# Sheet1.net
KiCad netlist of a schematic drawn in Altium Designer
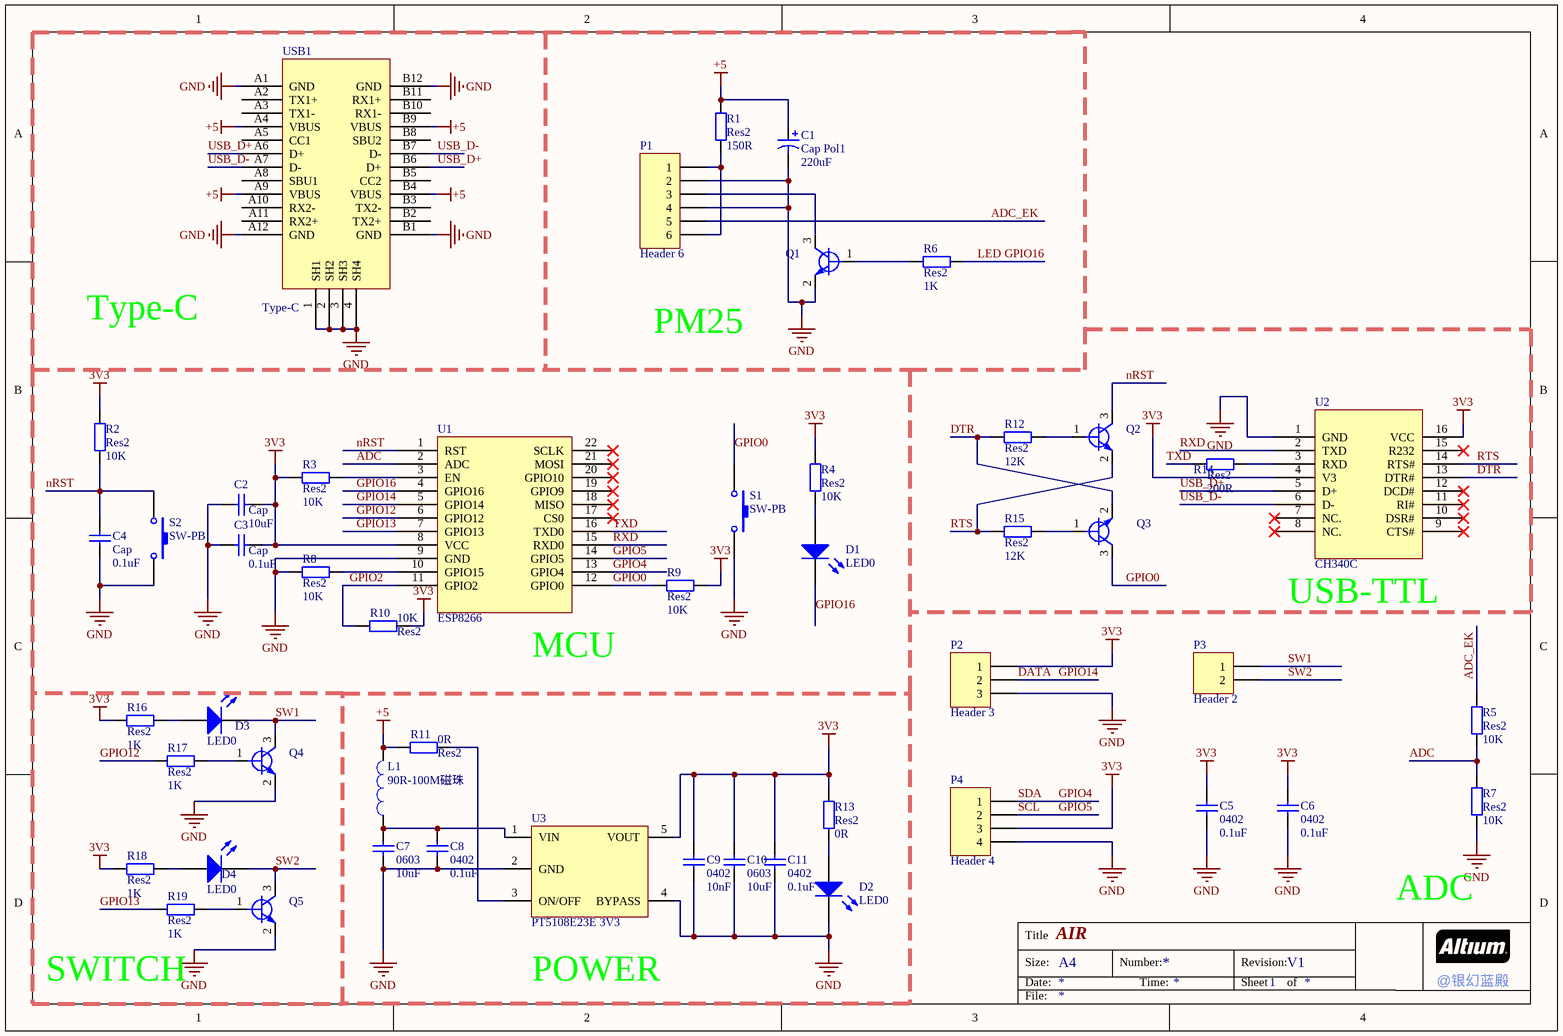
[diagram p0: Sheet1.SchDoc]

(export (version "E")
  (design (tool "Eeschema 10.0.6"))
  (components
    (comp (ref "C1")
      (value "Cap Pol1")
      (footprint "CAP 2.5*6.3*11.2")
      (description "Polarized Capacitor (Radial)")
      (fields (field (name "ALTIUM_VALUE") "220uF") (field (name "PUBLISHER") "Altium Limited"))
      (libsource (lib "Miscellaneous Devices") (part "Cap Pol1"))
    )
    (comp (ref "C2")
      (value "Cap")
      (footprint "C 0402_M")
      (description "Capacitor")
      (fields (field (name "ALTIUM_VALUE") "10uF") (field (name "PUBLISHER") "Altium Limited"))
      (libsource (lib "Miscellaneous Devices") (part "Cap"))
    )
    (comp (ref "C3")
      (value "Cap")
      (footprint "C 0402_M")
      (description "Capacitor")
      (fields (field (name "ALTIUM_VALUE") "0.1uF") (field (name "PUBLISHER") "Altium Limited"))
      (libsource (lib "Miscellaneous Devices") (part "Cap"))
    )
    (comp (ref "C4")
      (value "Cap")
      (footprint "C 0402_M")
      (description "Capacitor")
      (fields (field (name "ALTIUM_VALUE") "0.1uF") (field (name "PUBLISHER") "Altium Limited"))
      (libsource (lib "Miscellaneous Devices") (part "Cap"))
    )
    (comp (ref "C5")
      (value "0402")
      (footprint "C 0402_M")
      (description "Capacitor (Semiconductor SIM Model)")
      (fields (field (name "ALTIUM_VALUE") "0.1uF") (field (name "PUBLISHER") "Altium Limited"))
      (libsource (lib "Miscellaneous Devices") (part "Cap Semi"))
    )
    (comp (ref "C6")
      (value "0402")
      (footprint "C 0402_M")
      (description "Capacitor (Semiconductor SIM Model)")
      (fields (field (name "ALTIUM_VALUE") "0.1uF") (field (name "PUBLISHER") "Altium Limited"))
      (libsource (lib "Miscellaneous Devices") (part "Cap Semi"))
    )
    (comp (ref "C7")
      (value "0603")
      (footprint "C 0603_M")
      (description "Capacitor (Semiconductor SIM Model)")
      (fields (field (name "ALTIUM_VALUE") "10uF") (field (name "PUBLISHER") "Altium Limited"))
      (libsource (lib "Miscellaneous Devices") (part "Cap Semi"))
    )
    (comp (ref "C8")
      (value "0402")
      (footprint "C 0402_M")
      (description "Capacitor (Semiconductor SIM Model)")
      (fields (field (name "ALTIUM_VALUE") "0.1uF") (field (name "PUBLISHER") "Altium Limited"))
      (libsource (lib "Miscellaneous Devices") (part "Cap Semi"))
    )
    (comp (ref "C9")
      (value "0402")
      (footprint "C 0402_M")
      (description "Capacitor (Semiconductor SIM Model)")
      (fields (field (name "ALTIUM_VALUE") "10nF") (field (name "PUBLISHER") "Altium Limited"))
      (libsource (lib "Miscellaneous Devices") (part "Cap Semi"))
    )
    (comp (ref "C10")
      (value "0603")
      (footprint "C 0603_M")
      (description "Capacitor (Semiconductor SIM Model)")
      (fields (field (name "ALTIUM_VALUE") "10uF") (field (name "PUBLISHER") "Altium Limited"))
      (libsource (lib "Miscellaneous Devices") (part "Cap Semi"))
    )
    (comp (ref "C11")
      (value "0402")
      (footprint "C 0402_M")
      (description "Capacitor (Semiconductor SIM Model)")
      (fields (field (name "ALTIUM_VALUE") "0.1uF") (field (name "PUBLISHER") "Altium Limited"))
      (libsource (lib "Miscellaneous Devices") (part "Cap Semi"))
    )
    (comp (ref "D1")
      (value "LED0")
      (footprint "LED 0603R")
      (description "Typical INFRARED GaAs LED")
      (fields (field (name "PUBLISHER") "Altium Limited"))
      (libsource (lib "Miscellaneous Devices") (part "LED0"))
    )
    (comp (ref "D2")
      (value "LED0")
      (footprint "LED 0603R")
      (description "Typical INFRARED GaAs LED")
      (fields (field (name "PUBLISHER") "Altium Limited"))
      (libsource (lib "Miscellaneous Devices") (part "LED0"))
    )
    (comp (ref "D3")
      (value "LED0")
      (footprint "LED 0603R")
      (description "Typical INFRARED GaAs LED")
      (fields (field (name "PUBLISHER") "Altium Limited"))
      (libsource (lib "Miscellaneous Devices") (part "LED0"))
    )
    (comp (ref "D4")
      (value "LED0")
      (footprint "LED 0603R")
      (description "Typical INFRARED GaAs LED")
      (fields (field (name "PUBLISHER") "Altium Limited"))
      (libsource (lib "Miscellaneous Devices") (part "LED0"))
    )
    (comp (ref "L1")
      (value "90R-100M磁珠")
      (footprint "R 0603_M")
      (libsource (lib "手枪") (part "L,10UH,1.7A,S5*5*4.7,0.093Ω_1"))
    )
    (comp (ref "P1")
      (value "Header 6")
      (footprint "HDR1X6")
      (description "Header, 6-Pin")
      (fields (field (name "PUBLISHER") "Altium Limited"))
      (libsource (lib "Miscellaneous Connectors") (part "Header 6"))
    )
    (comp (ref "P2")
      (value "Header 3")
      (footprint "HDR1X3")
      (description "Header, 3-Pin")
      (fields (field (name "PUBLISHER") "Altium Limited"))
      (libsource (lib "Miscellaneous Connectors") (part "Header 3"))
    )
    (comp (ref "P3")
      (value "Header 2")
      (footprint "HDR1X2")
      (description "Header, 2-Pin")
      (fields (field (name "PUBLISHER") "Altium Limited"))
      (libsource (lib "Miscellaneous Connectors") (part "Header 2"))
    )
    (comp (ref "P4")
      (value "Header 4")
      (footprint "HDR1X4")
      (description "Header, 4-Pin")
      (fields (field (name "PUBLISHER") "Altium Limited"))
      (libsource (lib "Miscellaneous Connectors") (part "Header 4"))
    )
    (comp (ref "Q1")
      (value "Y1 NPN SOT23-3")
      (footprint "SMT_TRIODE_NPN")
      (libsource (lib "DDJ_20180904_Library") (part "S8050"))
    )
    (comp (ref "Q2")
      (value "Y1 NPN SOT23-3")
      (footprint "SMT_TRIODE_NPN")
      (libsource (lib "DDJ_20180904_Library") (part "S8050"))
    )
    (comp (ref "Q3")
      (value "Y1 NPN SOT23-3")
      (footprint "SMT_TRIODE_NPN")
      (libsource (lib "DDJ_20180904_Library") (part "S8050"))
    )
    (comp (ref "Q4")
      (value "Y1 NPN SOT23-3")
      (footprint "SMT_TRIODE_NPN")
      (libsource (lib "DDJ_20180904_Library") (part "S8050"))
    )
    (comp (ref "Q5")
      (value "Y1 NPN SOT23-3")
      (footprint "SMT_TRIODE_NPN")
      (libsource (lib "DDJ_20180904_Library") (part "S8050"))
    )
    (comp (ref "R1")
      (value "Res2")
      (footprint "R 0402_M")
      (description "Resistor")
      (fields (field (name "ALTIUM_VALUE") "150R") (field (name "PUBLISHER") "Altium Limited"))
      (libsource (lib "") (part "Res2_3"))
    )
    (comp (ref "R2")
      (value "Res2")
      (footprint "R 0402_M")
      (description "Resistor")
      (fields (field (name "ALTIUM_VALUE") "10K") (field (name "PUBLISHER") "Altium Limited"))
      (libsource (lib "") (part "Res2_2"))
    )
    (comp (ref "R3")
      (value "Res2")
      (footprint "R 0402_M")
      (description "Resistor")
      (fields (field (name "ALTIUM_VALUE") "10K") (field (name "PUBLISHER") "Altium Limited"))
      (libsource (lib "Miscellaneous Devices") (part "Res2"))
    )
    (comp (ref "R4")
      (value "Res2")
      (footprint "R 0402_M")
      (description "Resistor")
      (fields (field (name "ALTIUM_VALUE") "10K") (field (name "PUBLISHER") "Altium Limited"))
      (libsource (lib "") (part "Res2_2"))
    )
    (comp (ref "R5")
      (value "Res2")
      (footprint "R 0402_M")
      (description "Resistor")
      (fields (field (name "ALTIUM_VALUE") "10K") (field (name "PUBLISHER") "Altium Limited"))
      (libsource (lib "") (part "Res2_2"))
    )
    (comp (ref "R6")
      (value "Res2")
      (footprint "R 0402_M")
      (description "Resistor")
      (fields (field (name "ALTIUM_VALUE") "1K") (field (name "PUBLISHER") "Altium Limited"))
      (libsource (lib "") (part "Res2_1"))
    )
    (comp (ref "R7")
      (value "Res2")
      (footprint "R 0402_M")
      (description "Resistor")
      (fields (field (name "ALTIUM_VALUE") "10K") (field (name "PUBLISHER") "Altium Limited"))
      (libsource (lib "") (part "Res2_2"))
    )
    (comp (ref "R8")
      (value "Res2")
      (footprint "R 0402_M")
      (description "Resistor")
      (fields (field (name "ALTIUM_VALUE") "10K") (field (name "PUBLISHER") "Altium Limited"))
      (libsource (lib "Miscellaneous Devices") (part "Res2"))
    )
    (comp (ref "R9")
      (value "Res2")
      (footprint "R 0402_M")
      (description "Resistor")
      (fields (field (name "ALTIUM_VALUE") "10K") (field (name "PUBLISHER") "Altium Limited"))
      (libsource (lib "Miscellaneous Devices") (part "Res2"))
    )
    (comp (ref "R10")
      (value "Res2")
      (footprint "R 0402_M")
      (description "Resistor")
      (fields (field (name "ALTIUM_VALUE") "10K") (field (name "PUBLISHER") "Altium Limited"))
      (libsource (lib "Miscellaneous Devices") (part "Res2"))
    )
    (comp (ref "R11")
      (value "Res2")
      (footprint "R 0402_M")
      (description "Resistor")
      (fields (field (name "ALTIUM_VALUE") "0R") (field (name "PUBLISHER") "Altium Limited"))
      (libsource (lib "Miscellaneous Devices") (part "Res2"))
    )
    (comp (ref "R12")
      (value "Res2")
      (footprint "R 0402_M")
      (description "Resistor")
      (fields (field (name "ALTIUM_VALUE") "12K") (field (name "PUBLISHER") "Altium Limited"))
      (libsource (lib "") (part "Res2_1"))
    )
    (comp (ref "R13")
      (value "Res2")
      (footprint "R 0402_M")
      (description "Resistor")
      (fields (field (name "ALTIUM_VALUE") "0R") (field (name "PUBLISHER") "Altium Limited"))
      (libsource (lib "") (part "Res2_2"))
    )
    (comp (ref "R14")
      (value "Res2")
      (footprint "R 0402_M")
      (description "Resistor")
      (fields (field (name "ALTIUM_VALUE") "200R") (field (name "PUBLISHER") "Altium Limited"))
      (libsource (lib "") (part "Res2_1"))
    )
    (comp (ref "R15")
      (value "Res2")
      (footprint "R 0402_M")
      (description "Resistor")
      (fields (field (name "ALTIUM_VALUE") "12K") (field (name "PUBLISHER") "Altium Limited"))
      (libsource (lib "") (part "Res2_1"))
    )
    (comp (ref "R16")
      (value "Res2")
      (footprint "R 0402_M")
      (description "Resistor")
      (fields (field (name "ALTIUM_VALUE") "1K") (field (name "PUBLISHER") "Altium Limited"))
      (libsource (lib "") (part "Res2_1"))
    )
    (comp (ref "R17")
      (value "Res2")
      (footprint "R 0402_M")
      (description "Resistor")
      (fields (field (name "ALTIUM_VALUE") "1K") (field (name "PUBLISHER") "Altium Limited"))
      (libsource (lib "") (part "Res2_1"))
    )
    (comp (ref "R18")
      (value "Res2")
      (footprint "R 0402_M")
      (description "Resistor")
      (fields (field (name "ALTIUM_VALUE") "1K") (field (name "PUBLISHER") "Altium Limited"))
      (libsource (lib "") (part "Res2_1"))
    )
    (comp (ref "R19")
      (value "Res2")
      (footprint "R 0402_M")
      (description "Resistor")
      (fields (field (name "ALTIUM_VALUE") "1K") (field (name "PUBLISHER") "Altium Limited"))
      (libsource (lib "") (part "Res2_1"))
    )
    (comp (ref "S1")
      (value "SW-PB")
      (footprint "TSW DIP-6*6*5")
      (description "Switch")
      (fields (field (name "PUBLISHER") "Altium Limited"))
      (libsource (lib "Miscellaneous Devices") (part "SW-PB"))
    )
    (comp (ref "S2")
      (value "SW-PB")
      (footprint "TSW DIP-6*6*5")
      (description "Switch")
      (fields (field (name "PUBLISHER") "Altium Limited"))
      (libsource (lib "Miscellaneous Devices") (part "SW-PB"))
    )
    (comp (ref "U1") (value "ESP8266") (footprint "esp8266") (libsource (lib "HD") (part "ESP8266")))
    (comp (ref "U2") (value "CH340C") (footprint "CH340") (libsource (lib "HD") (part "CH340C")))
    (comp (ref "U3")
      (value "PT5108E23E 3V3")
      (footprint "SOT23-5")
      (description "LDO")
      (libsource (lib "MainBoard") (part "LP2992"))
    )
    (comp (ref "USB1")
      (value "Type-C")
      (footprint "Type-C-TOP")
      (libsource (lib "MainBoard") (part "USB-Type-C-TOP"))
    )
  )
  (nets
    (net (code "1") (name "+5") (class "Default")
      (node (ref "C1") (pin "1") (pinfunction "1_1") (pintype "passive"))
      (node (ref "L1") (pin "2") (pinfunction "2_2") (pintype "passive"))
      (node (ref "R1") (pin "2") (pinfunction "2_2") (pintype "passive"))
      (node (ref "R11") (pin "2") (pinfunction "2_2") (pintype "passive"))
      (node (ref "USB1") (pin "A4") (pinfunction "VBUS_A4") (pintype "passive"))
      (node (ref "USB1") (pin "A9") (pinfunction "VBUS_A9") (pintype "passive"))
      (node (ref "USB1") (pin "B4") (pinfunction "VBUS_B4") (pintype "passive"))
      (node (ref "USB1") (pin "B9") (pinfunction "VBUS_B9") (pintype "passive"))
    )
    (net (code "2") (name "/ADC") (class "Default")
      (node (ref "R5") (pin "2") (pinfunction "2_2") (pintype "passive"))
      (node (ref "R7") (pin "1") (pinfunction "1_1") (pintype "passive"))
      (node (ref "U1") (pin "2") (pinfunction "ADC_2") (pintype "passive"))
    )
    (net (code "3") (name "/ADC_EK") (class "Default")
      (node (ref "P1") (pin "5") (pinfunction "5_5") (pintype "passive"))
      (node (ref "R5") (pin "1") (pinfunction "1_1") (pintype "passive"))
    )
    (net (code "4") (name "/DATA") (class "Default")
      (node (ref "P2") (pin "2") (pinfunction "2_2") (pintype "passive"))
      (node (ref "U1") (pin "5") (pinfunction "GPIO14_5") (pintype "passive"))
    )
    (net (code "5") (name "/DTR") (class "Default")
      (node (ref "Q3") (pin "2") (pinfunction "EMITTER_2") (pintype "passive"))
      (node (ref "R12") (pin "1") (pinfunction "1_1") (pintype "passive"))
      (node (ref "U2") (pin "13") (pinfunction "DTR#_13") (pintype "passive"))
    )
    (net (code "6") (name "/GPIO0") (class "Default")
      (node (ref "Q3") (pin "3") (pinfunction "COLLECTOR_3") (pintype "passive"))
      (node (ref "R9") (pin "2") (pinfunction "2_2") (pintype "passive"))
      (node (ref "S1") (pin "1") (pinfunction "1_1") (pintype "passive"))
      (node (ref "U1") (pin "12") (pinfunction "GPIO0_12") (pintype "passive"))
    )
    (net (code "7") (name "/GPIO2") (class "Default")
      (node (ref "R10") (pin "2") (pinfunction "2_2") (pintype "passive"))
      (node (ref "U1") (pin "11") (pinfunction "GPIO2_11") (pintype "passive"))
    )
    (net (code "8") (name "/GPIO4") (class "Default")
      (node (ref "P4") (pin "1") (pinfunction "1_1") (pintype "passive"))
      (node (ref "U1") (pin "13") (pinfunction "GPIO4_13") (pintype "passive"))
    )
    (net (code "9") (name "/GPIO5") (class "Default")
      (node (ref "P4") (pin "2") (pinfunction "2_2") (pintype "passive"))
      (node (ref "U1") (pin "14") (pinfunction "GPIO5_14") (pintype "passive"))
    )
    (net (code "10") (name "/GPIO12") (class "Default")
      (node (ref "R17") (pin "1") (pinfunction "1_1") (pintype "passive"))
      (node (ref "U1") (pin "6") (pinfunction "GPIO12_6") (pintype "passive"))
    )
    (net (code "11") (name "/GPIO13") (class "Default")
      (node (ref "R19") (pin "1") (pinfunction "1_1") (pintype "passive"))
      (node (ref "U1") (pin "7") (pinfunction "GPIO13_7") (pintype "passive"))
    )
    (net (code "12") (name "/GPIO16") (class "Default")
      (node (ref "D1") (pin "2") (pinfunction "K_2") (pintype "passive"))
      (node (ref "R6") (pin "2") (pinfunction "2_2") (pintype "passive"))
      (node (ref "U1") (pin "4") (pinfunction "GPIO16_4") (pintype "passive"))
    )
    (net (code "13") (name "/RTS") (class "Default")
      (node (ref "Q2") (pin "2") (pinfunction "EMITTER_2") (pintype "passive"))
      (node (ref "R15") (pin "1") (pinfunction "1_1") (pintype "passive"))
      (node (ref "U2") (pin "14") (pinfunction "RTS#_14") (pintype "passive"))
    )
    (net (code "14") (name "/RXD") (class "Default")
      (node (ref "U1") (pin "15") (pinfunction "RXD0_15") (pintype "passive"))
      (node (ref "U2") (pin "2") (pinfunction "TXD_2") (pintype "passive"))
    )
    (net (code "15") (name "/SW1") (class "Default")
      (node (ref "D3") (pin "2") (pinfunction "K_2") (pintype "passive"))
      (node (ref "P3") (pin "1") (pinfunction "1_1") (pintype "passive"))
      (node (ref "Q4") (pin "3") (pinfunction "COLLECTOR_3") (pintype "passive"))
    )
    (net (code "16") (name "/SW2") (class "Default")
      (node (ref "D4") (pin "2") (pinfunction "K_2") (pintype "passive"))
      (node (ref "P3") (pin "2") (pinfunction "2_2") (pintype "passive"))
      (node (ref "Q5") (pin "3") (pinfunction "COLLECTOR_3") (pintype "passive"))
    )
    (net (code "17") (name "/TXD") (class "Default")
      (node (ref "R14") (pin "1") (pinfunction "1_1") (pintype "passive"))
      (node (ref "U1") (pin "16") (pinfunction "TXD0_16") (pintype "passive"))
    )
    (net (code "18") (name "/USB_D+") (class "Default")
      (node (ref "U2") (pin "5") (pinfunction "D+_5") (pintype "passive"))
      (node (ref "USB1") (pin "A6") (pinfunction "D+_A6") (pintype "passive"))
      (node (ref "USB1") (pin "B6") (pinfunction "D+_B6") (pintype "passive"))
    )
    (net (code "19") (name "/USB_D-") (class "Default")
      (node (ref "U2") (pin "6") (pinfunction "D-_6") (pintype "passive"))
      (node (ref "USB1") (pin "A7") (pinfunction "D-_A7") (pintype "passive"))
      (node (ref "USB1") (pin "B7") (pinfunction "D-_B7") (pintype "passive"))
    )
    (net (code "20") (name "/nRST") (class "Default")
      (node (ref "C4") (pin "2") (pinfunction "2_2") (pintype "passive"))
      (node (ref "Q2") (pin "3") (pinfunction "COLLECTOR_3") (pintype "passive"))
      (node (ref "R2") (pin "2") (pinfunction "2_2") (pintype "passive"))
      (node (ref "S2") (pin "1") (pinfunction "1_1") (pintype "passive"))
      (node (ref "U1") (pin "1") (pinfunction "RST_1") (pintype "passive"))
    )
    (net (code "21") (name "3V3") (class "Default")
      (node (ref "C10") (pin "2") (pinfunction "2_2") (pintype "passive"))
      (node (ref "C11") (pin "2") (pinfunction "2_2") (pintype "passive"))
      (node (ref "C2") (pin "2") (pinfunction "2_2") (pintype "passive"))
      (node (ref "C3") (pin "2") (pinfunction "2_2") (pintype "passive"))
      (node (ref "C5") (pin "2") (pinfunction "2_2") (pintype "passive"))
      (node (ref "C6") (pin "2") (pinfunction "2_2") (pintype "passive"))
      (node (ref "C9") (pin "2") (pinfunction "2_2") (pintype "passive"))
      (node (ref "P2") (pin "1") (pinfunction "1_1") (pintype "passive"))
      (node (ref "P4") (pin "3") (pinfunction "3_3") (pintype "passive"))
      (node (ref "R10") (pin "1") (pinfunction "1_1") (pintype "passive"))
      (node (ref "R13") (pin "1") (pinfunction "1_1") (pintype "passive"))
      (node (ref "R16") (pin "1") (pinfunction "1_1") (pintype "passive"))
      (node (ref "R18") (pin "1") (pinfunction "1_1") (pintype "passive"))
      (node (ref "R2") (pin "1") (pinfunction "1_1") (pintype "passive"))
      (node (ref "R3") (pin "2") (pinfunction "2_2") (pintype "passive"))
      (node (ref "R4") (pin "1") (pinfunction "1_1") (pintype "passive"))
      (node (ref "R9") (pin "1") (pinfunction "1_1") (pintype "passive"))
      (node (ref "U1") (pin "8") (pinfunction "VCC_8") (pintype "passive"))
      (node (ref "U2") (pin "16") (pinfunction "VCC_16") (pintype "passive"))
      (node (ref "U2") (pin "4") (pinfunction "V3_4") (pintype "passive"))
      (node (ref "U3") (pin "5") (pinfunction "VOUT_5") (pintype "passive"))
    )
    (net (code "22") (name "GND") (class "Default")
      (node (ref "C1") (pin "2") (pinfunction "2_2") (pintype "passive"))
      (node (ref "C10") (pin "1") (pinfunction "1_1") (pintype "passive"))
      (node (ref "C11") (pin "1") (pinfunction "1_1") (pintype "passive"))
      (node (ref "C2") (pin "1") (pinfunction "1_1") (pintype "passive"))
      (node (ref "C3") (pin "1") (pinfunction "1_1") (pintype "passive"))
      (node (ref "C4") (pin "1") (pinfunction "1_1") (pintype "passive"))
      (node (ref "C5") (pin "1") (pinfunction "1_1") (pintype "passive"))
      (node (ref "C6") (pin "1") (pinfunction "1_1") (pintype "passive"))
      (node (ref "C7") (pin "1") (pinfunction "1_1") (pintype "passive"))
      (node (ref "C8") (pin "1") (pinfunction "1_1") (pintype "passive"))
      (node (ref "C9") (pin "1") (pinfunction "1_1") (pintype "passive"))
      (node (ref "D2") (pin "2") (pinfunction "K_2") (pintype "passive"))
      (node (ref "P1") (pin "2") (pinfunction "2_2") (pintype "passive"))
      (node (ref "P1") (pin "4") (pinfunction "4_4") (pintype "passive"))
      (node (ref "P2") (pin "3") (pinfunction "3_3") (pintype "passive"))
      (node (ref "P4") (pin "4") (pinfunction "4_4") (pintype "passive"))
      (node (ref "Q1") (pin "2") (pinfunction "EMITTER_2") (pintype "passive"))
      (node (ref "Q4") (pin "2") (pinfunction "EMITTER_2") (pintype "passive"))
      (node (ref "Q5") (pin "2") (pinfunction "EMITTER_2") (pintype "passive"))
      (node (ref "R7") (pin "2") (pinfunction "2_2") (pintype "passive"))
      (node (ref "R8") (pin "2") (pinfunction "2_2") (pintype "passive"))
      (node (ref "S1") (pin "2") (pinfunction "2_2") (pintype "passive"))
      (node (ref "S2") (pin "2") (pinfunction "2_2") (pintype "passive"))
      (node (ref "U1") (pin "9") (pinfunction "GND_9") (pintype "passive"))
      (node (ref "U2") (pin "1") (pinfunction "GND_1") (pintype "passive"))
      (node (ref "U3") (pin "2") (pinfunction "GND_2") (pintype "passive"))
      (node (ref "U3") (pin "4") (pinfunction "BYPASS_4") (pintype "passive"))
      (node (ref "USB1") (pin "1") (pinfunction "SH1_1") (pintype "passive"))
      (node (ref "USB1") (pin "2") (pinfunction "SH2_2") (pintype "passive"))
      (node (ref "USB1") (pin "3") (pinfunction "SH3_3") (pintype "passive"))
      (node (ref "USB1") (pin "4") (pinfunction "SH4_4") (pintype "passive"))
      (node (ref "USB1") (pin "A1") (pinfunction "GND_A1") (pintype "passive"))
      (node (ref "USB1") (pin "A12") (pinfunction "GND_A12") (pintype "passive"))
      (node (ref "USB1") (pin "B1") (pinfunction "GND_B1") (pintype "passive"))
      (node (ref "USB1") (pin "B12") (pinfunction "GND_B12") (pintype "passive"))
    )
    (net (code "23") (name "Net-(D1-A)") (class "Default")
      (node (ref "D1") (pin "1") (pinfunction "A_1") (pintype "passive"))
      (node (ref "R4") (pin "2") (pinfunction "2_2") (pintype "passive"))
    )
    (net (code "24") (name "Net-(D2-A)") (class "Default")
      (node (ref "D2") (pin "1") (pinfunction "A_1") (pintype "passive"))
      (node (ref "R13") (pin "2") (pinfunction "2_2") (pintype "passive"))
    )
    (net (code "25") (name "Net-(D3-A)") (class "Default")
      (node (ref "D3") (pin "1") (pinfunction "A_1") (pintype "passive"))
      (node (ref "R16") (pin "2") (pinfunction "2_2") (pintype "passive"))
    )
    (net (code "26") (name "Net-(D4-A)") (class "Default")
      (node (ref "D4") (pin "1") (pinfunction "A_1") (pintype "passive"))
      (node (ref "R18") (pin "2") (pinfunction "2_2") (pintype "passive"))
    )
    (net (code "27") (name "Net-(P1-Pad1)") (class "Default")
      (node (ref "P1") (pin "1") (pinfunction "1_1") (pintype "passive"))
      (node (ref "P1") (pin "6") (pinfunction "6_6") (pintype "passive"))
      (node (ref "R1") (pin "1") (pinfunction "1_1") (pintype "passive"))
    )
    (net (code "28") (name "Net-(Q1-BASE)") (class "Default")
      (node (ref "Q1") (pin "1") (pinfunction "BASE_1") (pintype "passive"))
      (node (ref "R6") (pin "1") (pinfunction "1_1") (pintype "passive"))
    )
    (net (code "29") (name "Net-(Q1-COLLECTOR)") (class "Default")
      (node (ref "P1") (pin "3") (pinfunction "3_3") (pintype "passive"))
      (node (ref "Q1") (pin "3") (pinfunction "COLLECTOR_3") (pintype "passive"))
    )
    (net (code "30") (name "Net-(Q2-BASE)") (class "Default")
      (node (ref "Q2") (pin "1") (pinfunction "BASE_1") (pintype "passive"))
      (node (ref "R12") (pin "2") (pinfunction "2_2") (pintype "passive"))
    )
    (net (code "31") (name "Net-(Q3-BASE)") (class "Default")
      (node (ref "Q3") (pin "1") (pinfunction "BASE_1") (pintype "passive"))
      (node (ref "R15") (pin "2") (pinfunction "2_2") (pintype "passive"))
    )
    (net (code "32") (name "Net-(Q4-BASE)") (class "Default")
      (node (ref "Q4") (pin "1") (pinfunction "BASE_1") (pintype "passive"))
      (node (ref "R17") (pin "2") (pinfunction "2_2") (pintype "passive"))
    )
    (net (code "33") (name "Net-(Q5-BASE)") (class "Default")
      (node (ref "Q5") (pin "1") (pinfunction "BASE_1") (pintype "passive"))
      (node (ref "R19") (pin "2") (pinfunction "2_2") (pintype "passive"))
    )
    (net (code "34") (name "Net-(U1-EN)") (class "Default")
      (node (ref "R3") (pin "1") (pinfunction "1_1") (pintype "passive"))
      (node (ref "U1") (pin "3") (pinfunction "EN_3") (pintype "passive"))
    )
    (net (code "35") (name "Net-(U1-GPIO15)") (class "Default")
      (node (ref "R8") (pin "1") (pinfunction "1_1") (pintype "passive"))
      (node (ref "U1") (pin "10") (pinfunction "GPIO15_10") (pintype "passive"))
    )
    (net (code "36") (name "Net-(U2-RXD)") (class "Default")
      (node (ref "R14") (pin "2") (pinfunction "2_2") (pintype "passive"))
      (node (ref "U2") (pin "3") (pinfunction "RXD_3") (pintype "passive"))
    )
    (net (code "37") (name "Net-(U3-ON{slash}OFF)") (class "Default")
      (node (ref "R11") (pin "1") (pinfunction "1_1") (pintype "passive"))
      (node (ref "U3") (pin "3") (pinfunction "ON/OFF_3") (pintype "passive"))
    )
    (net (code "38") (name "Net-(U3-VIN)") (class "Default")
      (node (ref "C7") (pin "2") (pinfunction "2_2") (pintype "passive"))
      (node (ref "C8") (pin "2") (pinfunction "2_2") (pintype "passive"))
      (node (ref "L1") (pin "1") (pinfunction "1_1") (pintype "passive"))
      (node (ref "U3") (pin "1") (pinfunction "VIN_1") (pintype "passive"))
    )
    (net (code "39") (name "unconnected-(U1-CS0-Pad17)") (class "Default")
      (node (ref "U1") (pin "17") (pinfunction "CS0_17") (pintype "passive+no_connect"))
    )
    (net (code "40") (name "unconnected-(U1-GPIO9-Pad19)") (class "Default")
      (node (ref "U1") (pin "19") (pinfunction "GPIO9_19") (pintype "passive+no_connect"))
    )
    (net (code "41") (name "unconnected-(U1-GPIO10-Pad20)") (class "Default")
      (node (ref "U1") (pin "20") (pinfunction "GPIO10_20") (pintype "passive+no_connect"))
    )
    (net (code "42") (name "unconnected-(U1-MISO-Pad18)") (class "Default")
      (node (ref "U1") (pin "18") (pinfunction "MISO_18") (pintype "passive+no_connect"))
    )
    (net (code "43") (name "unconnected-(U1-MOSI-Pad21)") (class "Default")
      (node (ref "U1") (pin "21") (pinfunction "MOSI_21") (pintype "passive+no_connect"))
    )
    (net (code "44") (name "unconnected-(U1-SCLK-Pad22)") (class "Default")
      (node (ref "U1") (pin "22") (pinfunction "SCLK_22") (pintype "passive+no_connect"))
    )
    (net (code "45") (name "unconnected-(U2-CTS#-Pad9)") (class "Default")
      (node (ref "U2") (pin "9") (pinfunction "CTS#_9") (pintype "passive+no_connect"))
    )
    (net (code "46") (name "unconnected-(U2-DCD#-Pad12)") (class "Default")
      (node (ref "U2") (pin "12") (pinfunction "DCD#_12") (pintype "passive+no_connect"))
    )
    (net (code "47") (name "unconnected-(U2-DSR#-Pad10)") (class "Default")
      (node (ref "U2") (pin "10") (pinfunction "DSR#_10") (pintype "passive+no_connect"))
    )
    (net (code "48") (name "unconnected-(U2-NC.-Pad7)") (class "Default")
      (node (ref "U2") (pin "7") (pinfunction "NC._7") (pintype "passive+no_connect"))
    )
    (net (code "49") (name "unconnected-(U2-NC.-Pad8)") (class "Default")
      (node (ref "U2") (pin "8") (pinfunction "NC._8") (pintype "passive+no_connect"))
    )
    (net (code "50") (name "unconnected-(U2-R232-Pad15)") (class "Default")
      (node (ref "U2") (pin "15") (pinfunction "R232_15") (pintype "passive+no_connect"))
    )
    (net (code "51") (name "unconnected-(U2-RI#-Pad11)") (class "Default")
      (node (ref "U2") (pin "11") (pinfunction "RI#_11") (pintype "passive+no_connect"))
    )
    (net (code "52") (name "unconnected-(USB1-CC1-PadA5)") (class "Default")
      (node (ref "USB1") (pin "A5") (pinfunction "CC1_A5") (pintype "passive"))
    )
    (net (code "53") (name "unconnected-(USB1-CC2-PadB5)") (class "Default")
      (node (ref "USB1") (pin "B5") (pinfunction "CC2_B5") (pintype "passive"))
    )
    (net (code "54") (name "unconnected-(USB1-RX1+-PadB11)") (class "Default")
      (node (ref "USB1") (pin "B11") (pinfunction "RX1+_B11") (pintype "passive"))
    )
    (net (code "55") (name "unconnected-(USB1-RX1--PadB10)") (class "Default")
      (node (ref "USB1") (pin "B10") (pinfunction "RX1-_B10") (pintype "passive"))
    )
    (net (code "56") (name "unconnected-(USB1-RX2+-PadA11)") (class "Default")
      (node (ref "USB1") (pin "A11") (pinfunction "RX2+_A11") (pintype "passive"))
    )
    (net (code "57") (name "unconnected-(USB1-RX2--PadA10)") (class "Default")
      (node (ref "USB1") (pin "A10") (pinfunction "RX2-_A10") (pintype "passive"))
    )
    (net (code "58") (name "unconnected-(USB1-SBU1-PadA8)") (class "Default")
      (node (ref "USB1") (pin "A8") (pinfunction "SBU1_A8") (pintype "passive"))
    )
    (net (code "59") (name "unconnected-(USB1-SBU2-PadB8)") (class "Default")
      (node (ref "USB1") (pin "B8") (pinfunction "SBU2_B8") (pintype "passive"))
    )
    (net (code "60") (name "unconnected-(USB1-TX1+-PadA2)") (class "Default")
      (node (ref "USB1") (pin "A2") (pinfunction "TX1+_A2") (pintype "passive"))
    )
    (net (code "61") (name "unconnected-(USB1-TX1--PadA3)") (class "Default")
      (node (ref "USB1") (pin "A3") (pinfunction "TX1-_A3") (pintype "passive"))
    )
    (net (code "62") (name "unconnected-(USB1-TX2+-PadB2)") (class "Default")
      (node (ref "USB1") (pin "B2") (pinfunction "TX2+_B2") (pintype "passive"))
    )
    (net (code "63") (name "unconnected-(USB1-TX2--PadB3)") (class "Default")
      (node (ref "USB1") (pin "B3") (pinfunction "TX2-_B3") (pintype "passive"))
    )
  )
)
